# BreakoutBoard.net
KiCad netlist of a schematic drawn in EAGLE
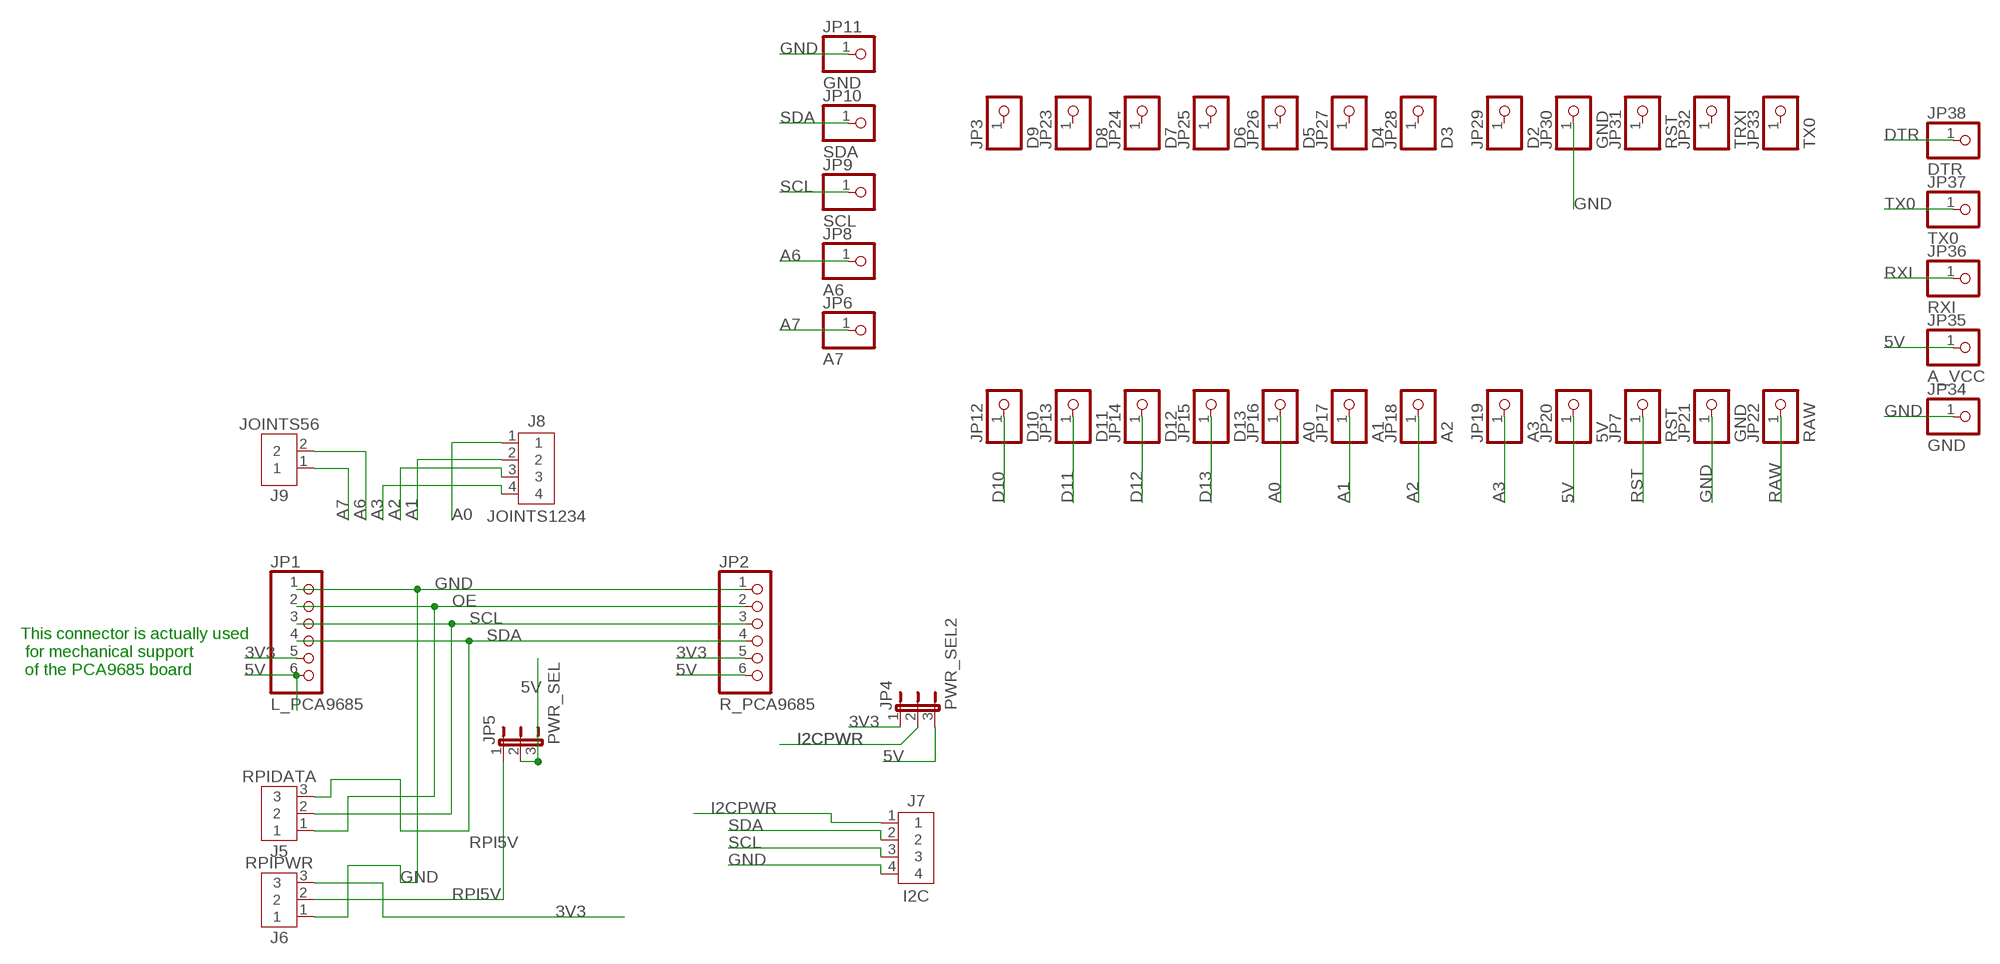
[diagram p0: schematic, sheet 1]

(export (version "E")
  (design (tool "Eeschema 10.0.6"))
  (components
    (comp (ref "J5")
      (value "RPIDATA")
      (footprint "eagle-import:B3B-XH-A")
      (fields (field (name "MANUFACTURER") "JST (XH connector)") (field (name "MPN") "B3B-XH-A"))
      (libsource (lib "eagle-import") (part "B3B-XH-A"))
    )
    (comp (ref "J6")
      (value "RPIPWR")
      (footprint "eagle-import:B3B-XH-A")
      (fields (field (name "MANUFACTURER") "JST (XH connector)") (field (name "MPN") "B3B-XH-A"))
      (libsource (lib "eagle-import") (part "B3B-XH-A"))
    )
    (comp (ref "J7")
      (value "I2C")
      (footprint "eagle-import:B4B-XH-A")
      (fields (field (name "MANUFACTURER") "JST (XH connector)") (field (name "MPN") "B4B-XH-A"))
      (libsource (lib "eagle-import") (part "B4B-XH-A"))
    )
    (comp (ref "J8")
      (value "JOINTS1234")
      (footprint "eagle-import:B4B-XH-A")
      (fields (field (name "MANUFACTURER") "JST (XH connector)") (field (name "MPN") "B4B-XH-A"))
      (libsource (lib "eagle-import") (part "B4B-XH-A"))
    )
    (comp (ref "J9")
      (value "JOINTS56")
      (footprint "eagle-import:B2B-XH-A")
      (fields (field (name "MANUFACTURER") "JST (XH CONNECTOR)") (field (name "MPN") "B2B-XH-A"))
      (libsource (lib "eagle-import") (part "B2B-XH-A"))
    )
    (comp (ref "JP1")
      (value "L_PCA9685")
      (footprint "eagle-import:1X06")
      (libsource (lib "eagle-import") (part "PINHD-1X6"))
    )
    (comp (ref "JP2")
      (value "R_PCA9685")
      (footprint "eagle-import:1X06")
      (libsource (lib "eagle-import") (part "PINHD-1X6"))
    )
    (comp (ref "JP3")
      (value "D9")
      (footprint "eagle-import:1X01")
      (libsource (lib "eagle-import") (part "PINHD-1X1"))
    )
    (comp (ref "JP4")
      (value "PWR_SEL2")
      (footprint "eagle-import:JP2")
      (libsource (lib "eagle-import") (part "JP2E"))
    )
    (comp (ref "JP5")
      (value "PWR_SEL")
      (footprint "eagle-import:JP2")
      (libsource (lib "eagle-import") (part "JP2E"))
    )
    (comp (ref "JP6")
      (value "A7")
      (footprint "eagle-import:1X01")
      (libsource (lib "eagle-import") (part "PINHD-1X1"))
    )
    (comp (ref "JP7")
      (value "RST")
      (footprint "eagle-import:1X01")
      (libsource (lib "eagle-import") (part "PINHD-1X1"))
    )
    (comp (ref "JP8")
      (value "A6")
      (footprint "eagle-import:1X01")
      (libsource (lib "eagle-import") (part "PINHD-1X1"))
    )
    (comp (ref "JP9")
      (value "SCL")
      (footprint "eagle-import:1X01")
      (libsource (lib "eagle-import") (part "PINHD-1X1"))
    )
    (comp (ref "JP10")
      (value "SDA")
      (footprint "eagle-import:1X01")
      (libsource (lib "eagle-import") (part "PINHD-1X1"))
    )
    (comp (ref "JP11")
      (value "GND")
      (footprint "eagle-import:1X01")
      (libsource (lib "eagle-import") (part "PINHD-1X1"))
    )
    (comp (ref "JP12")
      (value "D10")
      (footprint "eagle-import:1X01")
      (libsource (lib "eagle-import") (part "PINHD-1X1"))
    )
    (comp (ref "JP13")
      (value "D11")
      (footprint "eagle-import:1X01")
      (libsource (lib "eagle-import") (part "PINHD-1X1"))
    )
    (comp (ref "JP14")
      (value "D12")
      (footprint "eagle-import:1X01")
      (libsource (lib "eagle-import") (part "PINHD-1X1"))
    )
    (comp (ref "JP15")
      (value "D13")
      (footprint "eagle-import:1X01")
      (libsource (lib "eagle-import") (part "PINHD-1X1"))
    )
    (comp (ref "JP16")
      (value "A0")
      (footprint "eagle-import:1X01")
      (libsource (lib "eagle-import") (part "PINHD-1X1"))
    )
    (comp (ref "JP17")
      (value "A1")
      (footprint "eagle-import:1X01")
      (libsource (lib "eagle-import") (part "PINHD-1X1"))
    )
    (comp (ref "JP18")
      (value "A2")
      (footprint "eagle-import:1X01")
      (libsource (lib "eagle-import") (part "PINHD-1X1"))
    )
    (comp (ref "JP19")
      (value "A3")
      (footprint "eagle-import:1X01")
      (libsource (lib "eagle-import") (part "PINHD-1X1"))
    )
    (comp (ref "JP20")
      (value "5V")
      (footprint "eagle-import:1X01")
      (libsource (lib "eagle-import") (part "PINHD-1X1"))
    )
    (comp (ref "JP21")
      (value "GND")
      (footprint "eagle-import:1X01")
      (libsource (lib "eagle-import") (part "PINHD-1X1"))
    )
    (comp (ref "JP22")
      (value "RAW")
      (footprint "eagle-import:1X01")
      (libsource (lib "eagle-import") (part "PINHD-1X1"))
    )
    (comp (ref "JP23")
      (value "D8")
      (footprint "eagle-import:1X01")
      (libsource (lib "eagle-import") (part "PINHD-1X1"))
    )
    (comp (ref "JP24")
      (value "D7")
      (footprint "eagle-import:1X01")
      (libsource (lib "eagle-import") (part "PINHD-1X1"))
    )
    (comp (ref "JP25")
      (value "D6")
      (footprint "eagle-import:1X01")
      (libsource (lib "eagle-import") (part "PINHD-1X1"))
    )
    (comp (ref "JP26")
      (value "D5")
      (footprint "eagle-import:1X01")
      (libsource (lib "eagle-import") (part "PINHD-1X1"))
    )
    (comp (ref "JP27")
      (value "D4")
      (footprint "eagle-import:1X01")
      (libsource (lib "eagle-import") (part "PINHD-1X1"))
    )
    (comp (ref "JP28")
      (value "D3")
      (footprint "eagle-import:1X01")
      (libsource (lib "eagle-import") (part "PINHD-1X1"))
    )
    (comp (ref "JP29")
      (value "D2")
      (footprint "eagle-import:1X01")
      (libsource (lib "eagle-import") (part "PINHD-1X1"))
    )
    (comp (ref "JP30")
      (value "GND")
      (footprint "eagle-import:1X01")
      (libsource (lib "eagle-import") (part "PINHD-1X1"))
    )
    (comp (ref "JP31")
      (value "RST")
      (footprint "eagle-import:1X01")
      (libsource (lib "eagle-import") (part "PINHD-1X1"))
    )
    (comp (ref "JP32")
      (value "TRXI")
      (footprint "eagle-import:1X01")
      (libsource (lib "eagle-import") (part "PINHD-1X1"))
    )
    (comp (ref "JP33")
      (value "TX0")
      (footprint "eagle-import:1X01")
      (libsource (lib "eagle-import") (part "PINHD-1X1"))
    )
    (comp (ref "JP34")
      (value "GND")
      (footprint "eagle-import:1X01")
      (libsource (lib "eagle-import") (part "PINHD-1X1"))
    )
    (comp (ref "JP35")
      (value "A_VCC")
      (footprint "eagle-import:1X01")
      (libsource (lib "eagle-import") (part "PINHD-1X1"))
    )
    (comp (ref "JP36")
      (value "RXI")
      (footprint "eagle-import:1X01")
      (libsource (lib "eagle-import") (part "PINHD-1X1"))
    )
    (comp (ref "JP37")
      (value "TX0")
      (footprint "eagle-import:1X01")
      (libsource (lib "eagle-import") (part "PINHD-1X1"))
    )
    (comp (ref "JP38")
      (value "DTR")
      (footprint "eagle-import:1X01")
      (libsource (lib "eagle-import") (part "PINHD-1X1"))
    )
  )
  (nets
    (net (code "1") (name "/3V3") (class "Default")
      (node (ref "J6") (pin "3") (pinfunction "3_3") (pintype "bidirectional"))
      (node (ref "JP1") (pin "5") (pinfunction "5_5") (pintype "passive"))
      (node (ref "JP2") (pin "5") (pinfunction "5_5") (pintype "passive"))
      (node (ref "JP4") (pin "1") (pinfunction "1_1") (pintype "passive"))
    )
    (net (code "2") (name "/5V") (class "Default")
      (node (ref "JP1") (pin "6") (pinfunction "6_6") (pintype "passive"))
      (node (ref "JP2") (pin "6") (pinfunction "6_6") (pintype "passive"))
      (node (ref "JP20") (pin "1") (pinfunction "1_1") (pintype "passive"))
      (node (ref "JP35") (pin "1") (pinfunction "1_1") (pintype "passive"))
      (node (ref "JP4") (pin "3") (pinfunction "3_3") (pintype "passive"))
      (node (ref "JP5") (pin "2") (pinfunction "2_2") (pintype "passive"))
      (node (ref "JP5") (pin "3") (pinfunction "3_3") (pintype "passive"))
    )
    (net (code "3") (name "/A0") (class "Default")
      (node (ref "J8") (pin "1") (pinfunction "1_1") (pintype "bidirectional"))
      (node (ref "JP16") (pin "1") (pinfunction "1_1") (pintype "passive"))
    )
    (net (code "4") (name "/A1") (class "Default")
      (node (ref "J8") (pin "2") (pinfunction "2_2") (pintype "bidirectional"))
      (node (ref "JP17") (pin "1") (pinfunction "1_1") (pintype "passive"))
    )
    (net (code "5") (name "/A2") (class "Default")
      (node (ref "J8") (pin "3") (pinfunction "3_3") (pintype "bidirectional"))
      (node (ref "JP18") (pin "1") (pinfunction "1_1") (pintype "passive"))
    )
    (net (code "6") (name "/A3") (class "Default")
      (node (ref "J8") (pin "4") (pinfunction "4_4") (pintype "bidirectional"))
      (node (ref "JP19") (pin "1") (pinfunction "1_1") (pintype "passive"))
    )
    (net (code "7") (name "/A6") (class "Default")
      (node (ref "J9") (pin "2") (pinfunction "2_2") (pintype "bidirectional"))
      (node (ref "JP8") (pin "1") (pinfunction "1_1") (pintype "passive"))
    )
    (net (code "8") (name "/A7") (class "Default")
      (node (ref "J9") (pin "1") (pinfunction "1_1") (pintype "bidirectional"))
      (node (ref "JP6") (pin "1") (pinfunction "1_1") (pintype "passive"))
    )
    (net (code "9") (name "/D10") (class "Default")
      (node (ref "JP12") (pin "1") (pinfunction "1_1") (pintype "passive"))
    )
    (net (code "10") (name "/D11") (class "Default")
      (node (ref "JP13") (pin "1") (pinfunction "1_1") (pintype "passive"))
    )
    (net (code "11") (name "/D12") (class "Default")
      (node (ref "JP14") (pin "1") (pinfunction "1_1") (pintype "passive"))
    )
    (net (code "12") (name "/D13") (class "Default")
      (node (ref "JP15") (pin "1") (pinfunction "1_1") (pintype "passive"))
    )
    (net (code "13") (name "/DTR") (class "Default")
      (node (ref "JP38") (pin "1") (pinfunction "1_1") (pintype "passive"))
    )
    (net (code "14") (name "/GND") (class "Default")
      (node (ref "J6") (pin "1") (pinfunction "1_1") (pintype "bidirectional"))
      (node (ref "J7") (pin "4") (pinfunction "4_4") (pintype "bidirectional"))
      (node (ref "JP1") (pin "1") (pinfunction "1_1") (pintype "passive"))
      (node (ref "JP11") (pin "1") (pinfunction "1_1") (pintype "passive"))
      (node (ref "JP2") (pin "1") (pinfunction "1_1") (pintype "passive"))
      (node (ref "JP21") (pin "1") (pinfunction "1_1") (pintype "passive"))
      (node (ref "JP30") (pin "1") (pinfunction "1_1") (pintype "passive"))
      (node (ref "JP34") (pin "1") (pinfunction "1_1") (pintype "passive"))
    )
    (net (code "15") (name "/I2CPWR") (class "Default")
      (node (ref "J7") (pin "1") (pinfunction "1_1") (pintype "bidirectional"))
      (node (ref "JP4") (pin "2") (pinfunction "2_2") (pintype "passive"))
    )
    (net (code "16") (name "/OE") (class "Default")
      (node (ref "J5") (pin "1") (pinfunction "1_1") (pintype "bidirectional"))
      (node (ref "JP1") (pin "2") (pinfunction "2_2") (pintype "passive"))
      (node (ref "JP2") (pin "2") (pinfunction "2_2") (pintype "passive"))
    )
    (net (code "17") (name "/RAW") (class "Default")
      (node (ref "JP22") (pin "1") (pinfunction "1_1") (pintype "passive"))
    )
    (net (code "18") (name "/RPI5V") (class "Default")
      (node (ref "J6") (pin "2") (pinfunction "2_2") (pintype "bidirectional"))
      (node (ref "JP5") (pin "1") (pinfunction "1_1") (pintype "passive"))
    )
    (net (code "19") (name "/RST") (class "Default")
      (node (ref "JP7") (pin "1") (pinfunction "1_1") (pintype "passive"))
    )
    (net (code "20") (name "/RXI") (class "Default")
      (node (ref "JP36") (pin "1") (pinfunction "1_1") (pintype "passive"))
    )
    (net (code "21") (name "/SCL") (class "Default")
      (node (ref "J5") (pin "2") (pinfunction "2_2") (pintype "bidirectional"))
      (node (ref "J7") (pin "3") (pinfunction "3_3") (pintype "bidirectional"))
      (node (ref "JP1") (pin "3") (pinfunction "3_3") (pintype "passive"))
      (node (ref "JP2") (pin "3") (pinfunction "3_3") (pintype "passive"))
      (node (ref "JP9") (pin "1") (pinfunction "1_1") (pintype "passive"))
    )
    (net (code "22") (name "/SDA") (class "Default")
      (node (ref "J5") (pin "3") (pinfunction "3_3") (pintype "bidirectional"))
      (node (ref "J7") (pin "2") (pinfunction "2_2") (pintype "bidirectional"))
      (node (ref "JP1") (pin "4") (pinfunction "4_4") (pintype "passive"))
      (node (ref "JP10") (pin "1") (pinfunction "1_1") (pintype "passive"))
      (node (ref "JP2") (pin "4") (pinfunction "4_4") (pintype "passive"))
    )
    (net (code "23") (name "/TX0") (class "Default")
      (node (ref "JP37") (pin "1") (pinfunction "1_1") (pintype "passive"))
    )
    (net (code "24") (name "unconnected-(JP3-Pad1)") (class "Default")
      (node (ref "JP3") (pin "1") (pinfunction "1_1") (pintype "passive"))
    )
    (net (code "25") (name "unconnected-(JP23-Pad1)") (class "Default")
      (node (ref "JP23") (pin "1") (pinfunction "1_1") (pintype "passive"))
    )
    (net (code "26") (name "unconnected-(JP24-Pad1)") (class "Default")
      (node (ref "JP24") (pin "1") (pinfunction "1_1") (pintype "passive"))
    )
    (net (code "27") (name "unconnected-(JP25-Pad1)") (class "Default")
      (node (ref "JP25") (pin "1") (pinfunction "1_1") (pintype "passive"))
    )
    (net (code "28") (name "unconnected-(JP26-Pad1)") (class "Default")
      (node (ref "JP26") (pin "1") (pinfunction "1_1") (pintype "passive"))
    )
    (net (code "29") (name "unconnected-(JP27-Pad1)") (class "Default")
      (node (ref "JP27") (pin "1") (pinfunction "1_1") (pintype "passive"))
    )
    (net (code "30") (name "unconnected-(JP28-Pad1)") (class "Default")
      (node (ref "JP28") (pin "1") (pinfunction "1_1") (pintype "passive"))
    )
    (net (code "31") (name "unconnected-(JP29-Pad1)") (class "Default")
      (node (ref "JP29") (pin "1") (pinfunction "1_1") (pintype "passive"))
    )
    (net (code "32") (name "unconnected-(JP31-Pad1)") (class "Default")
      (node (ref "JP31") (pin "1") (pinfunction "1_1") (pintype "passive"))
    )
    (net (code "33") (name "unconnected-(JP32-Pad1)") (class "Default")
      (node (ref "JP32") (pin "1") (pinfunction "1_1") (pintype "passive"))
    )
    (net (code "34") (name "unconnected-(JP33-Pad1)") (class "Default")
      (node (ref "JP33") (pin "1") (pinfunction "1_1") (pintype "passive"))
    )
  )
)
